# 07-KSZ9031_1G_BASET_XCVR.net
KiCad netlist of a schematic drawn in Altium Designer
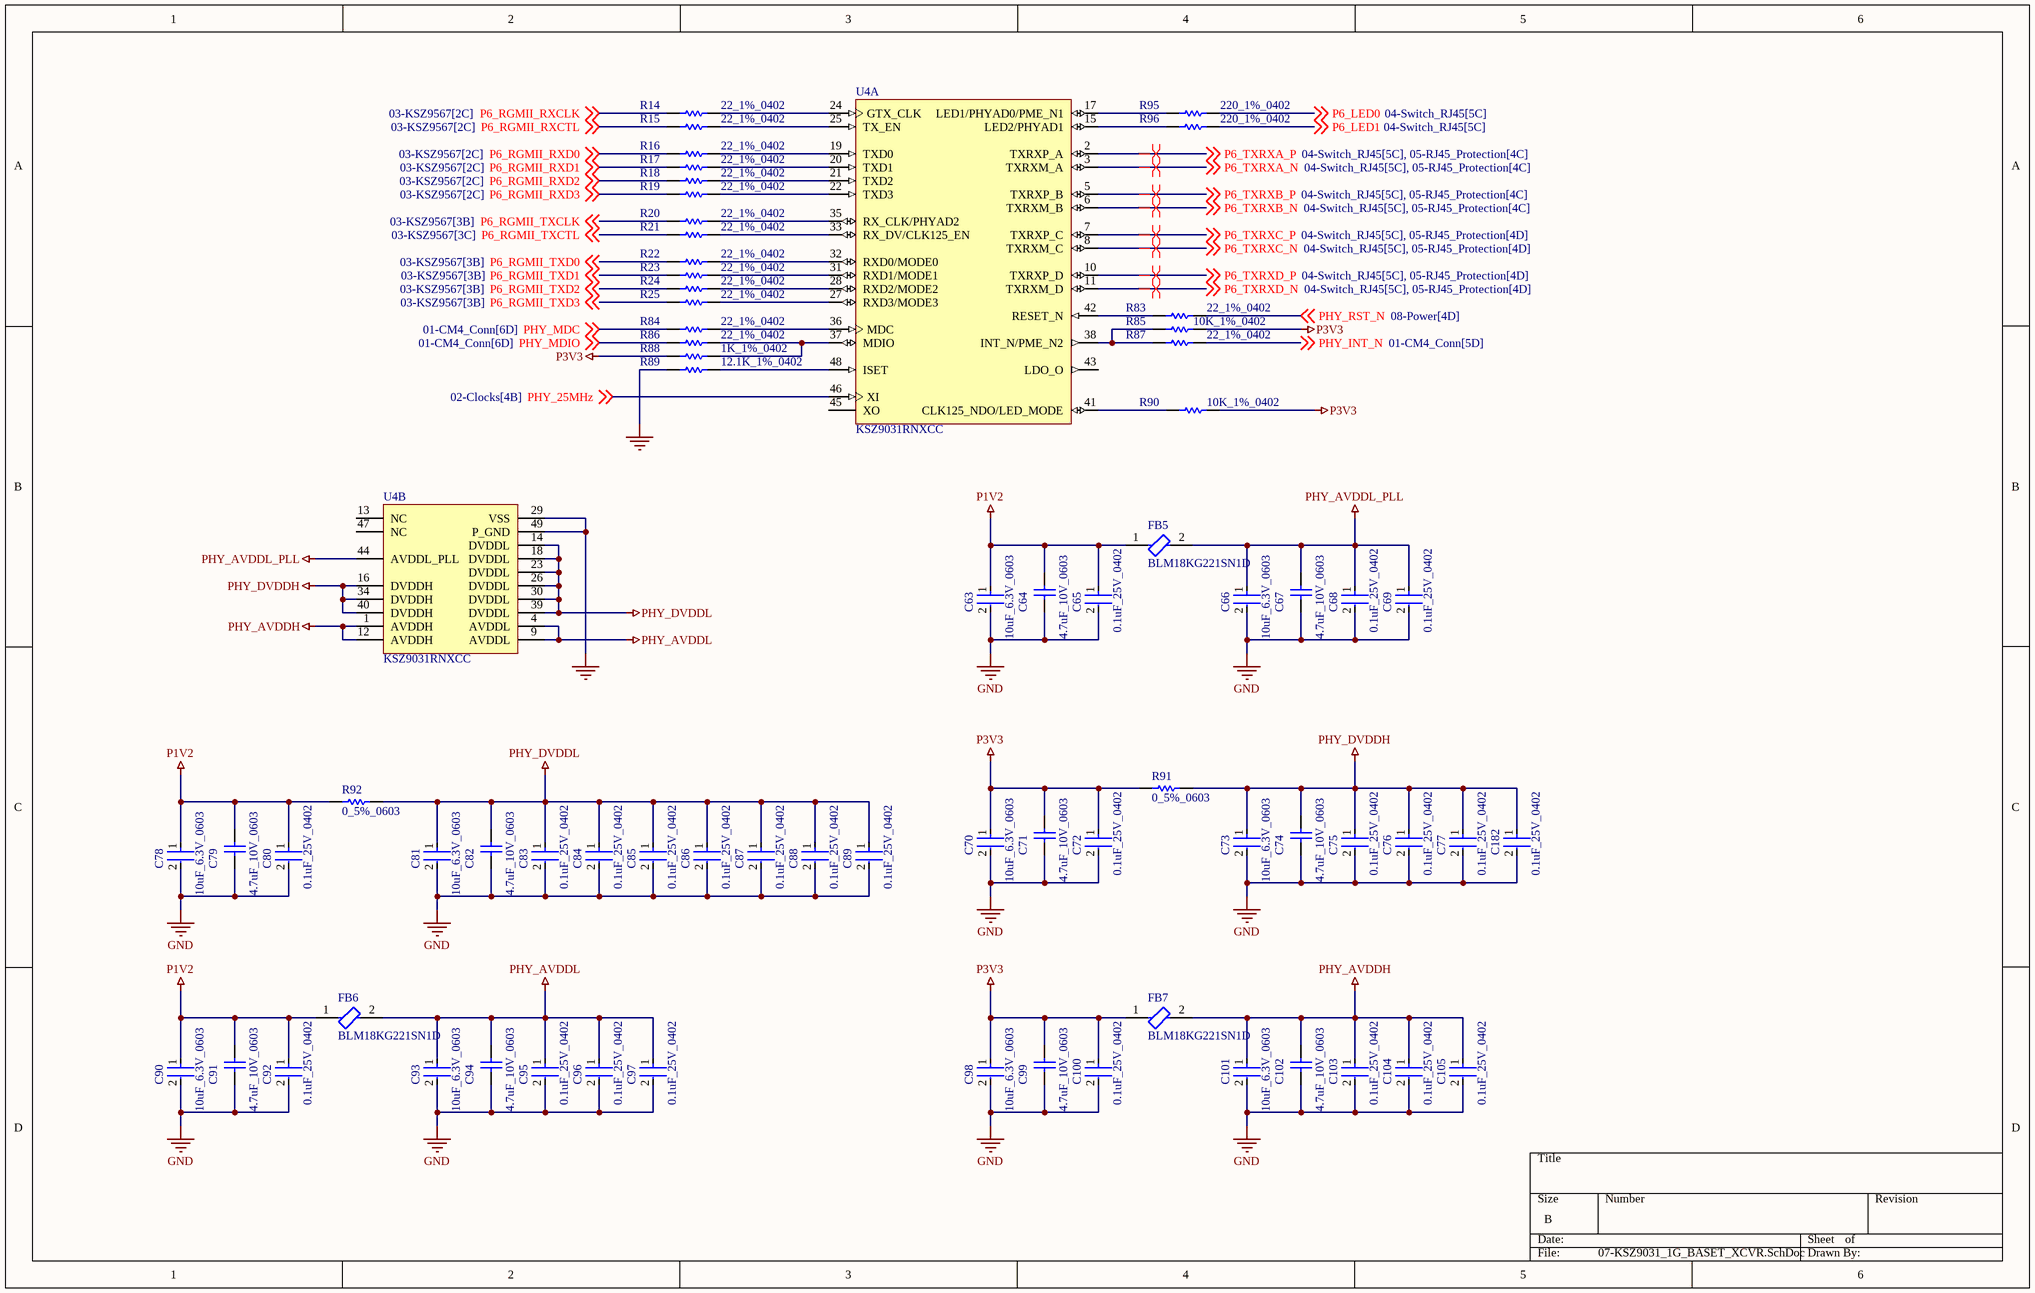
[diagram p0: 07-KSZ9031_1G_BASET_XCVR.SchDoc]

(export (version "E")
  (design (tool "Eeschema 10.0.6"))
  (components
    (comp (ref "C63")
      (value "10uF_6.3V_0603")
      (footprint "FP-C0603C106M9PACTU-MFG")
      (description "CAP CER 10UF 6.3V X5R 0603")
      (fields
        (field (name "MANUFACTURER PART NUMBER") "C0603C106M9PACTU")
        (field (name "MANUFACTURER") "Kemet")
      )
      (libsource (lib "Altium Content Vault") (part "b4654b650e69147ec39a6b967a45e02"))
    )
    (comp (ref "C64")
      (value "4.7uF_10V_0603")
      (footprint "CAPC1608X87X35NL15T15")
      (fields (field (name "PART NUMBER") "C0603C475K8PACTU") (field (name "MANUFACTURER") "Kemet"))
      (libsource (lib "Altium Content Vault") (part "CAP"))
    )
    (comp (ref "C65")
      (value "0.1uF_25V_0402")
      (footprint "FP-0402-L_1_0_1-W_0_5_0_1-IPC_C")
      (description "General Purpose Ceramic Capacitor, 0402, 100nF, 10%, X7R, 15%, 25V")
      (fields (field (name "VOLTAGE") "25V") (field (name "TOLERANCE") "10%"))
      (libsource (lib "Altium Content Vault") (part "b4654b650e69147ec39a6b967a45e02"))
    )
    (comp (ref "C66")
      (value "10uF_6.3V_0603")
      (footprint "FP-C0603C106M9PACTU-MFG")
      (description "CAP CER 10UF 6.3V X5R 0603")
      (fields
        (field (name "MANUFACTURER PART NUMBER") "C0603C106M9PACTU")
        (field (name "MANUFACTURER") "Kemet")
      )
      (libsource (lib "Altium Content Vault") (part "b4654b650e69147ec39a6b967a45e02"))
    )
    (comp (ref "C67")
      (value "4.7uF_10V_0603")
      (footprint "CAPC1608X87X35NL15T15")
      (fields (field (name "PART NUMBER") "C0603C475K8PACTU") (field (name "MANUFACTURER") "Kemet"))
      (libsource (lib "Altium Content Vault") (part "CAP"))
    )
    (comp (ref "C68")
      (value "0.1uF_25V_0402")
      (footprint "FP-0402-L_1_0_1-W_0_5_0_1-IPC_C")
      (description "General Purpose Ceramic Capacitor, 0402, 100nF, 10%, X7R, 15%, 25V")
      (fields (field (name "VOLTAGE") "25V") (field (name "TOLERANCE") "10%"))
      (libsource (lib "Altium Content Vault") (part "b4654b650e69147ec39a6b967a45e02"))
    )
    (comp (ref "C69")
      (value "0.1uF_25V_0402")
      (footprint "FP-0402-L_1_0_1-W_0_5_0_1-IPC_C")
      (description "General Purpose Ceramic Capacitor, 0402, 100nF, 10%, X7R, 15%, 25V")
      (fields (field (name "VOLTAGE") "25V") (field (name "TOLERANCE") "10%"))
      (libsource (lib "Altium Content Vault") (part "b4654b650e69147ec39a6b967a45e02"))
    )
    (comp (ref "C70")
      (value "10uF_6.3V_0603")
      (footprint "FP-C0603C106M9PACTU-MFG")
      (description "CAP CER 10UF 6.3V X5R 0603")
      (fields
        (field (name "MANUFACTURER PART NUMBER") "C0603C106M9PACTU")
        (field (name "MANUFACTURER") "Kemet")
      )
      (libsource (lib "Altium Content Vault") (part "b4654b650e69147ec39a6b967a45e02"))
    )
    (comp (ref "C71")
      (value "4.7uF_10V_0603")
      (footprint "CAPC1608X87X35NL15T15")
      (fields (field (name "PART NUMBER") "C0603C475K8PACTU") (field (name "MANUFACTURER") "Kemet"))
      (libsource (lib "Altium Content Vault") (part "CAP"))
    )
    (comp (ref "C72")
      (value "0.1uF_25V_0402")
      (footprint "FP-0402-L_1_0_1-W_0_5_0_1-IPC_C")
      (description "General Purpose Ceramic Capacitor, 0402, 100nF, 10%, X7R, 15%, 25V")
      (fields (field (name "VOLTAGE") "25V") (field (name "TOLERANCE") "10%"))
      (libsource (lib "Altium Content Vault") (part "b4654b650e69147ec39a6b967a45e02"))
    )
    (comp (ref "C73")
      (value "10uF_6.3V_0603")
      (footprint "FP-C0603C106M9PACTU-MFG")
      (description "CAP CER 10UF 6.3V X5R 0603")
      (fields
        (field (name "MANUFACTURER PART NUMBER") "C0603C106M9PACTU")
        (field (name "MANUFACTURER") "Kemet")
      )
      (libsource (lib "Altium Content Vault") (part "b4654b650e69147ec39a6b967a45e02"))
    )
    (comp (ref "C74")
      (value "4.7uF_10V_0603")
      (footprint "CAPC1608X87X35NL15T15")
      (fields (field (name "PART NUMBER") "C0603C475K8PACTU") (field (name "MANUFACTURER") "Kemet"))
      (libsource (lib "Altium Content Vault") (part "CAP"))
    )
    (comp (ref "C75")
      (value "0.1uF_25V_0402")
      (footprint "FP-0402-L_1_0_1-W_0_5_0_1-IPC_C")
      (description "General Purpose Ceramic Capacitor, 0402, 100nF, 10%, X7R, 15%, 25V")
      (fields (field (name "VOLTAGE") "25V") (field (name "TOLERANCE") "10%"))
      (libsource (lib "Altium Content Vault") (part "b4654b650e69147ec39a6b967a45e02"))
    )
    (comp (ref "C76")
      (value "0.1uF_25V_0402")
      (footprint "FP-0402-L_1_0_1-W_0_5_0_1-IPC_C")
      (description "General Purpose Ceramic Capacitor, 0402, 100nF, 10%, X7R, 15%, 25V")
      (fields (field (name "VOLTAGE") "25V") (field (name "TOLERANCE") "10%"))
      (libsource (lib "Altium Content Vault") (part "b4654b650e69147ec39a6b967a45e02"))
    )
    (comp (ref "C77")
      (value "0.1uF_25V_0402")
      (footprint "FP-0402-L_1_0_1-W_0_5_0_1-IPC_C")
      (description "General Purpose Ceramic Capacitor, 0402, 100nF, 10%, X7R, 15%, 25V")
      (fields (field (name "VOLTAGE") "25V") (field (name "TOLERANCE") "10%"))
      (libsource (lib "Altium Content Vault") (part "b4654b650e69147ec39a6b967a45e02"))
    )
    (comp (ref "C78")
      (value "10uF_6.3V_0603")
      (footprint "FP-C0603C106M9PACTU-MFG")
      (description "CAP CER 10UF 6.3V X5R 0603")
      (fields
        (field (name "MANUFACTURER PART NUMBER") "C0603C106M9PACTU")
        (field (name "MANUFACTURER") "Kemet")
      )
      (libsource (lib "Altium Content Vault") (part "b4654b650e69147ec39a6b967a45e02"))
    )
    (comp (ref "C79")
      (value "4.7uF_10V_0603")
      (footprint "CAPC1608X87X35NL15T15")
      (fields (field (name "PART NUMBER") "C0603C475K8PACTU") (field (name "MANUFACTURER") "Kemet"))
      (libsource (lib "Altium Content Vault") (part "CAP"))
    )
    (comp (ref "C80")
      (value "0.1uF_25V_0402")
      (footprint "FP-0402-L_1_0_1-W_0_5_0_1-IPC_C")
      (description "General Purpose Ceramic Capacitor, 0402, 100nF, 10%, X7R, 15%, 25V")
      (fields (field (name "VOLTAGE") "25V") (field (name "TOLERANCE") "10%"))
      (libsource (lib "Altium Content Vault") (part "b4654b650e69147ec39a6b967a45e02"))
    )
    (comp (ref "C81")
      (value "10uF_6.3V_0603")
      (footprint "FP-C0603C106M9PACTU-MFG")
      (description "CAP CER 10UF 6.3V X5R 0603")
      (fields
        (field (name "MANUFACTURER PART NUMBER") "C0603C106M9PACTU")
        (field (name "MANUFACTURER") "Kemet")
      )
      (libsource (lib "Altium Content Vault") (part "b4654b650e69147ec39a6b967a45e02"))
    )
    (comp (ref "C82")
      (value "4.7uF_10V_0603")
      (footprint "CAPC1608X87X35NL15T15")
      (fields (field (name "PART NUMBER") "C0603C475K8PACTU") (field (name "MANUFACTURER") "Kemet"))
      (libsource (lib "Altium Content Vault") (part "CAP"))
    )
    (comp (ref "C83")
      (value "0.1uF_25V_0402")
      (footprint "FP-0402-L_1_0_1-W_0_5_0_1-IPC_C")
      (description "General Purpose Ceramic Capacitor, 0402, 100nF, 10%, X7R, 15%, 25V")
      (fields (field (name "VOLTAGE") "25V") (field (name "TOLERANCE") "10%"))
      (libsource (lib "Altium Content Vault") (part "b4654b650e69147ec39a6b967a45e02"))
    )
    (comp (ref "C84")
      (value "0.1uF_25V_0402")
      (footprint "FP-0402-L_1_0_1-W_0_5_0_1-IPC_C")
      (description "General Purpose Ceramic Capacitor, 0402, 100nF, 10%, X7R, 15%, 25V")
      (fields (field (name "VOLTAGE") "25V") (field (name "TOLERANCE") "10%"))
      (libsource (lib "Altium Content Vault") (part "b4654b650e69147ec39a6b967a45e02"))
    )
    (comp (ref "C85")
      (value "0.1uF_25V_0402")
      (footprint "FP-0402-L_1_0_1-W_0_5_0_1-IPC_C")
      (description "General Purpose Ceramic Capacitor, 0402, 100nF, 10%, X7R, 15%, 25V")
      (fields (field (name "VOLTAGE") "25V") (field (name "TOLERANCE") "10%"))
      (libsource (lib "Altium Content Vault") (part "b4654b650e69147ec39a6b967a45e02"))
    )
    (comp (ref "C86")
      (value "0.1uF_25V_0402")
      (footprint "FP-0402-L_1_0_1-W_0_5_0_1-IPC_C")
      (description "General Purpose Ceramic Capacitor, 0402, 100nF, 10%, X7R, 15%, 25V")
      (fields (field (name "VOLTAGE") "25V") (field (name "TOLERANCE") "10%"))
      (libsource (lib "Altium Content Vault") (part "b4654b650e69147ec39a6b967a45e02"))
    )
    (comp (ref "C87")
      (value "0.1uF_25V_0402")
      (footprint "FP-0402-L_1_0_1-W_0_5_0_1-IPC_C")
      (description "General Purpose Ceramic Capacitor, 0402, 100nF, 10%, X7R, 15%, 25V")
      (fields (field (name "VOLTAGE") "25V") (field (name "TOLERANCE") "10%"))
      (libsource (lib "Altium Content Vault") (part "b4654b650e69147ec39a6b967a45e02"))
    )
    (comp (ref "C88")
      (value "0.1uF_25V_0402")
      (footprint "FP-0402-L_1_0_1-W_0_5_0_1-IPC_C")
      (description "General Purpose Ceramic Capacitor, 0402, 100nF, 10%, X7R, 15%, 25V")
      (fields (field (name "VOLTAGE") "25V") (field (name "TOLERANCE") "10%"))
      (libsource (lib "Altium Content Vault") (part "b4654b650e69147ec39a6b967a45e02"))
    )
    (comp (ref "C89")
      (value "0.1uF_25V_0402")
      (footprint "FP-0402-L_1_0_1-W_0_5_0_1-IPC_C")
      (description "General Purpose Ceramic Capacitor, 0402, 100nF, 10%, X7R, 15%, 25V")
      (fields (field (name "VOLTAGE") "25V") (field (name "TOLERANCE") "10%"))
      (libsource (lib "Altium Content Vault") (part "b4654b650e69147ec39a6b967a45e02"))
    )
    (comp (ref "C90")
      (value "10uF_6.3V_0603")
      (footprint "FP-C0603C106M9PACTU-MFG")
      (description "CAP CER 10UF 6.3V X5R 0603")
      (fields
        (field (name "MANUFACTURER PART NUMBER") "C0603C106M9PACTU")
        (field (name "MANUFACTURER") "Kemet")
      )
      (libsource (lib "Altium Content Vault") (part "b4654b650e69147ec39a6b967a45e02"))
    )
    (comp (ref "C91")
      (value "4.7uF_10V_0603")
      (footprint "CAPC1608X87X35NL15T15")
      (fields (field (name "PART NUMBER") "C0603C475K8PACTU") (field (name "MANUFACTURER") "Kemet"))
      (libsource (lib "Altium Content Vault") (part "CAP"))
    )
    (comp (ref "C92")
      (value "0.1uF_25V_0402")
      (footprint "FP-0402-L_1_0_1-W_0_5_0_1-IPC_C")
      (description "General Purpose Ceramic Capacitor, 0402, 100nF, 10%, X7R, 15%, 25V")
      (fields (field (name "VOLTAGE") "25V") (field (name "TOLERANCE") "10%"))
      (libsource (lib "Altium Content Vault") (part "b4654b650e69147ec39a6b967a45e02"))
    )
    (comp (ref "C93")
      (value "10uF_6.3V_0603")
      (footprint "FP-C0603C106M9PACTU-MFG")
      (description "CAP CER 10UF 6.3V X5R 0603")
      (fields
        (field (name "MANUFACTURER PART NUMBER") "C0603C106M9PACTU")
        (field (name "MANUFACTURER") "Kemet")
      )
      (libsource (lib "Altium Content Vault") (part "b4654b650e69147ec39a6b967a45e02"))
    )
    (comp (ref "C94")
      (value "4.7uF_10V_0603")
      (footprint "CAPC1608X87X35NL15T15")
      (fields (field (name "PART NUMBER") "C0603C475K8PACTU") (field (name "MANUFACTURER") "Kemet"))
      (libsource (lib "Altium Content Vault") (part "CAP"))
    )
    (comp (ref "C95")
      (value "0.1uF_25V_0402")
      (footprint "FP-0402-L_1_0_1-W_0_5_0_1-IPC_C")
      (description "General Purpose Ceramic Capacitor, 0402, 100nF, 10%, X7R, 15%, 25V")
      (fields (field (name "VOLTAGE") "25V") (field (name "TOLERANCE") "10%"))
      (libsource (lib "Altium Content Vault") (part "b4654b650e69147ec39a6b967a45e02"))
    )
    (comp (ref "C96")
      (value "0.1uF_25V_0402")
      (footprint "FP-0402-L_1_0_1-W_0_5_0_1-IPC_C")
      (description "General Purpose Ceramic Capacitor, 0402, 100nF, 10%, X7R, 15%, 25V")
      (fields (field (name "VOLTAGE") "25V") (field (name "TOLERANCE") "10%"))
      (libsource (lib "Altium Content Vault") (part "b4654b650e69147ec39a6b967a45e02"))
    )
    (comp (ref "C97")
      (value "0.1uF_25V_0402")
      (footprint "FP-0402-L_1_0_1-W_0_5_0_1-IPC_C")
      (description "General Purpose Ceramic Capacitor, 0402, 100nF, 10%, X7R, 15%, 25V")
      (fields (field (name "VOLTAGE") "25V") (field (name "TOLERANCE") "10%"))
      (libsource (lib "Altium Content Vault") (part "b4654b650e69147ec39a6b967a45e02"))
    )
    (comp (ref "C98")
      (value "10uF_6.3V_0603")
      (footprint "FP-C0603C106M9PACTU-MFG")
      (description "CAP CER 10UF 6.3V X5R 0603")
      (fields
        (field (name "MANUFACTURER PART NUMBER") "C0603C106M9PACTU")
        (field (name "MANUFACTURER") "Kemet")
      )
      (libsource (lib "Altium Content Vault") (part "b4654b650e69147ec39a6b967a45e02"))
    )
    (comp (ref "C99")
      (value "4.7uF_10V_0603")
      (footprint "CAPC1608X87X35NL15T15")
      (fields (field (name "PART NUMBER") "C0603C475K8PACTU") (field (name "MANUFACTURER") "Kemet"))
      (libsource (lib "Altium Content Vault") (part "CAP"))
    )
    (comp (ref "C100")
      (value "0.1uF_25V_0402")
      (footprint "FP-0402-L_1_0_1-W_0_5_0_1-IPC_C")
      (description "General Purpose Ceramic Capacitor, 0402, 100nF, 10%, X7R, 15%, 25V")
      (fields (field (name "VOLTAGE") "25V") (field (name "TOLERANCE") "10%"))
      (libsource (lib "Altium Content Vault") (part "b4654b650e69147ec39a6b967a45e02"))
    )
    (comp (ref "C101")
      (value "10uF_6.3V_0603")
      (footprint "FP-C0603C106M9PACTU-MFG")
      (description "CAP CER 10UF 6.3V X5R 0603")
      (fields
        (field (name "MANUFACTURER PART NUMBER") "C0603C106M9PACTU")
        (field (name "MANUFACTURER") "Kemet")
      )
      (libsource (lib "Altium Content Vault") (part "b4654b650e69147ec39a6b967a45e02"))
    )
    (comp (ref "C102")
      (value "4.7uF_10V_0603")
      (footprint "CAPC1608X87X35NL15T15")
      (fields (field (name "PART NUMBER") "C0603C475K8PACTU") (field (name "MANUFACTURER") "Kemet"))
      (libsource (lib "Altium Content Vault") (part "CAP"))
    )
    (comp (ref "C103")
      (value "0.1uF_25V_0402")
      (footprint "FP-0402-L_1_0_1-W_0_5_0_1-IPC_C")
      (description "General Purpose Ceramic Capacitor, 0402, 100nF, 10%, X7R, 15%, 25V")
      (fields (field (name "VOLTAGE") "25V") (field (name "TOLERANCE") "10%"))
      (libsource (lib "Altium Content Vault") (part "b4654b650e69147ec39a6b967a45e02"))
    )
    (comp (ref "C104")
      (value "0.1uF_25V_0402")
      (footprint "FP-0402-L_1_0_1-W_0_5_0_1-IPC_C")
      (description "General Purpose Ceramic Capacitor, 0402, 100nF, 10%, X7R, 15%, 25V")
      (fields (field (name "VOLTAGE") "25V") (field (name "TOLERANCE") "10%"))
      (libsource (lib "Altium Content Vault") (part "b4654b650e69147ec39a6b967a45e02"))
    )
    (comp (ref "C105")
      (value "0.1uF_25V_0402")
      (footprint "FP-0402-L_1_0_1-W_0_5_0_1-IPC_C")
      (description "General Purpose Ceramic Capacitor, 0402, 100nF, 10%, X7R, 15%, 25V")
      (fields (field (name "VOLTAGE") "25V") (field (name "TOLERANCE") "10%"))
      (libsource (lib "Altium Content Vault") (part "b4654b650e69147ec39a6b967a45e02"))
    )
    (comp (ref "C182")
      (value "0.1uF_25V_0402")
      (footprint "FP-0402-L_1_0_1-W_0_5_0_1-IPC_C")
      (description "General Purpose Ceramic Capacitor, 0402, 100nF, 10%, X7R, 15%, 25V")
      (fields (field (name "VOLTAGE") "25V") (field (name "TOLERANCE") "10%"))
      (libsource (lib "Altium Content Vault") (part "b4654b650e69147ec39a6b967a45e02"))
    )
    (comp (ref "FB5")
      (value "BLM18KG221SN1D")
      (footprint "FP-BLM18-0_15-t0_8-IPC_B")
      (description "Chip Ferrite Bead, 0603, 220Ω @ 100MHz, 0.05Ω, 25%, 2.2A")
      (fields (field (name "TOLERANCE") "25%"))
      (libsource (lib "Altium Content Vault") (part "5f30dd21d616792df468990f7003faa"))
    )
    (comp (ref "FB6")
      (value "BLM18KG221SN1D")
      (footprint "FP-BLM18-0_15-t0_8-IPC_B")
      (description "Chip Ferrite Bead, 0603, 220Ω @ 100MHz, 0.05Ω, 25%, 2.2A")
      (fields (field (name "TOLERANCE") "25%"))
      (libsource (lib "Altium Content Vault") (part "5f30dd21d616792df468990f7003faa"))
    )
    (comp (ref "FB7")
      (value "BLM18KG221SN1D")
      (footprint "FP-BLM18-0_15-t0_8-IPC_B")
      (description "Chip Ferrite Bead, 0603, 220Ω @ 100MHz, 0.05Ω, 25%, 2.2A")
      (fields (field (name "TOLERANCE") "25%"))
      (libsource (lib "Altium Content Vault") (part "5f30dd21d616792df468990f7003faa"))
    )
    (comp (ref "R14")
      (value "22_1%_0402")
      (footprint "RESC1005X40X25ML05T10")
      (fields (field (name "PART NUMBER") "RC0402FR-1322RL") (field (name "MANUFACTURER") "Yageo / Phycomp"))
      (libsource (lib "Altium Content Vault") (part "RES"))
    )
    (comp (ref "R15")
      (value "22_1%_0402")
      (footprint "RESC1005X40X25ML05T10")
      (fields (field (name "PART NUMBER") "RC0402FR-1322RL") (field (name "MANUFACTURER") "Yageo / Phycomp"))
      (libsource (lib "Altium Content Vault") (part "RES"))
    )
    (comp (ref "R16")
      (value "22_1%_0402")
      (footprint "RESC1005X40X25ML05T10")
      (fields (field (name "PART NUMBER") "RC0402FR-1322RL") (field (name "MANUFACTURER") "Yageo / Phycomp"))
      (libsource (lib "Altium Content Vault") (part "RES"))
    )
    (comp (ref "R17")
      (value "22_1%_0402")
      (footprint "RESC1005X40X25ML05T10")
      (fields (field (name "PART NUMBER") "RC0402FR-1322RL") (field (name "MANUFACTURER") "Yageo / Phycomp"))
      (libsource (lib "Altium Content Vault") (part "RES"))
    )
    (comp (ref "R18")
      (value "22_1%_0402")
      (footprint "RESC1005X40X25ML05T10")
      (fields (field (name "PART NUMBER") "RC0402FR-1322RL") (field (name "MANUFACTURER") "Yageo / Phycomp"))
      (libsource (lib "Altium Content Vault") (part "RES"))
    )
    (comp (ref "R19")
      (value "22_1%_0402")
      (footprint "RESC1005X40X25ML05T10")
      (fields (field (name "PART NUMBER") "RC0402FR-1322RL") (field (name "MANUFACTURER") "Yageo / Phycomp"))
      (libsource (lib "Altium Content Vault") (part "RES"))
    )
    (comp (ref "R20")
      (value "22_1%_0402")
      (footprint "RESC1005X40X25ML05T10")
      (fields (field (name "PART NUMBER") "RC0402FR-1322RL") (field (name "MANUFACTURER") "Yageo / Phycomp"))
      (libsource (lib "Altium Content Vault") (part "RES"))
    )
    (comp (ref "R21")
      (value "22_1%_0402")
      (footprint "RESC1005X40X25ML05T10")
      (fields (field (name "PART NUMBER") "RC0402FR-1322RL") (field (name "MANUFACTURER") "Yageo / Phycomp"))
      (libsource (lib "Altium Content Vault") (part "RES"))
    )
    (comp (ref "R22")
      (value "22_1%_0402")
      (footprint "RESC1005X40X25ML05T10")
      (fields (field (name "PART NUMBER") "RC0402FR-1322RL") (field (name "MANUFACTURER") "Yageo / Phycomp"))
      (libsource (lib "Altium Content Vault") (part "RES"))
    )
    (comp (ref "R23")
      (value "22_1%_0402")
      (footprint "RESC1005X40X25ML05T10")
      (fields (field (name "PART NUMBER") "RC0402FR-1322RL") (field (name "MANUFACTURER") "Yageo / Phycomp"))
      (libsource (lib "Altium Content Vault") (part "RES"))
    )
    (comp (ref "R24")
      (value "22_1%_0402")
      (footprint "RESC1005X40X25ML05T10")
      (fields (field (name "PART NUMBER") "RC0402FR-1322RL") (field (name "MANUFACTURER") "Yageo / Phycomp"))
      (libsource (lib "Altium Content Vault") (part "RES"))
    )
    (comp (ref "R25")
      (value "22_1%_0402")
      (footprint "RESC1005X40X25ML05T10")
      (fields (field (name "PART NUMBER") "RC0402FR-1322RL") (field (name "MANUFACTURER") "Yageo / Phycomp"))
      (libsource (lib "Altium Content Vault") (part "RES"))
    )
    (comp (ref "R83")
      (value "22_1%_0402")
      (footprint "RESC1005X40X25ML05T10")
      (fields (field (name "PART NUMBER") "RC0402FR-1322RL") (field (name "MANUFACTURER") "Yageo / Phycomp"))
      (libsource (lib "Altium Content Vault") (part "RES"))
    )
    (comp (ref "R84")
      (value "22_1%_0402")
      (footprint "RESC1005X40X25ML05T10")
      (fields (field (name "PART NUMBER") "RC0402FR-1322RL") (field (name "MANUFACTURER") "Yageo / Phycomp"))
      (libsource (lib "Altium Content Vault") (part "RES"))
    )
    (comp (ref "R85")
      (value "10K_1%_0402")
      (footprint "RESC1005X40X25NL10T10")
      (fields (field (name "MANUFACTURER") "Bourns") (field (name "PART NUMBER") "CR0402-FX-1002GLF"))
      (libsource (lib "Altium Content Vault") (part "RES"))
    )
    (comp (ref "R86")
      (value "22_1%_0402")
      (footprint "RESC1005X40X25ML05T10")
      (fields (field (name "PART NUMBER") "RC0402FR-1322RL") (field (name "MANUFACTURER") "Yageo / Phycomp"))
      (libsource (lib "Altium Content Vault") (part "RES"))
    )
    (comp (ref "R87")
      (value "22_1%_0402")
      (footprint "RESC1005X40X25ML05T10")
      (fields (field (name "PART NUMBER") "RC0402FR-1322RL") (field (name "MANUFACTURER") "Yageo / Phycomp"))
      (libsource (lib "Altium Content Vault") (part "RES"))
    )
    (comp (ref "R88")
      (value "1K_1%_0402")
      (footprint "RESC1005X40X25ML05T10")
      (fields (field (name "MANUFACTURER") "Multicomp") (field (name "PART NUMBER") "MCMR04X1001FTL"))
      (libsource (lib "Altium Content Vault") (part "RES"))
    )
    (comp (ref "R89")
      (value "12.1K_1%_0402")
      (footprint "RESC1005X40X25NL10T10")
      (fields (field (name "MANUFACTURER") "Multicomp") (field (name "PART NUMBER") "MC00625W0402112K1"))
      (libsource (lib "Altium Content Vault") (part "RES"))
    )
    (comp (ref "R90")
      (value "10K_1%_0402")
      (footprint "RESC1005X40X25NL10T10")
      (fields (field (name "MANUFACTURER") "Bourns") (field (name "PART NUMBER") "CR0402-FX-1002GLF"))
      (libsource (lib "Altium Content Vault") (part "RES"))
    )
    (comp (ref "R91")
      (value "0_5%_0603")
      (footprint "RESC1608X55X25ML10T15")
      (description "Chip Resistor, 0 Ohm, +/- 5%, 0.1 W, -55 to 155 degC, 0603 (1608 Metric), RoHS, Tape and Reel")
      (fields (field (name "TOLERANCE") "5%") (field (name "MANUFACTURER") "Yageo"))
      (libsource (lib "Altium Content Vault") (part "RES-2"))
    )
    (comp (ref "R92")
      (value "0_5%_0603")
      (footprint "RESC1608X55X25ML10T15")
      (description "Chip Resistor, 0 Ohm, +/- 5%, 0.1 W, -55 to 155 degC, 0603 (1608 Metric), RoHS, Tape and Reel")
      (fields (field (name "TOLERANCE") "5%") (field (name "MANUFACTURER") "Yageo"))
      (libsource (lib "Altium Content Vault") (part "RES-2"))
    )
    (comp (ref "R95")
      (value "220_1%_0402")
      (footprint "RESC1005X40X25NL05T10")
      (fields (field (name "MANUFACTURER") "Yageo / Phycomp") (field (name "PART NUMBER") "RC0402JR-07220RL"))
      (libsource (lib "Altium Content Vault") (part "RES"))
    )
    (comp (ref "R96")
      (value "220_1%_0402")
      (footprint "RESC1005X40X25NL05T10")
      (fields (field (name "MANUFACTURER") "Yageo / Phycomp") (field (name "PART NUMBER") "RC0402JR-07220RL"))
      (libsource (lib "Altium Content Vault") (part "RES"))
    )
    (comp (ref "U4")
      (value "KSZ9031RNXCC")
      (footprint "MICL-QFN-48_V")
      (description "Gigabit Ethernet Transceiver with RGMII Support, 1.14 to 1.26 V, 0 to 70 degC, 48-Pin QFN, RoHS")
      (fields (field (name "MANUFACTURER") "Micrel"))
      (libsource (lib "Altium Content Vault") (part "MICL-KSZ9031RNX-48"))
    )
  )
  (nets
    (net (code "1") (name "GND") (class "Default")
      (node (ref "C100") (pin "2") (pinfunction "2_2") (pintype "passive"))
      (node (ref "C101") (pin "2") (pinfunction "2_2") (pintype "passive"))
      (node (ref "C102") (pin "1") (pinfunction "1_1") (pintype "passive"))
      (node (ref "C103") (pin "2") (pinfunction "2_2") (pintype "passive"))
      (node (ref "C104") (pin "2") (pinfunction "2_2") (pintype "passive"))
      (node (ref "C105") (pin "2") (pinfunction "2_2") (pintype "passive"))
      (node (ref "C182") (pin "2") (pinfunction "2_2") (pintype "passive"))
      (node (ref "C63") (pin "2") (pinfunction "2_2") (pintype "passive"))
      (node (ref "C64") (pin "1") (pinfunction "1_1") (pintype "passive"))
      (node (ref "C65") (pin "2") (pinfunction "2_2") (pintype "passive"))
      (node (ref "C66") (pin "2") (pinfunction "2_2") (pintype "passive"))
      (node (ref "C67") (pin "1") (pinfunction "1_1") (pintype "passive"))
      (node (ref "C68") (pin "2") (pinfunction "2_2") (pintype "passive"))
      (node (ref "C69") (pin "2") (pinfunction "2_2") (pintype "passive"))
      (node (ref "C70") (pin "2") (pinfunction "2_2") (pintype "passive"))
      (node (ref "C71") (pin "1") (pinfunction "1_1") (pintype "passive"))
      (node (ref "C72") (pin "2") (pinfunction "2_2") (pintype "passive"))
      (node (ref "C73") (pin "2") (pinfunction "2_2") (pintype "passive"))
      (node (ref "C74") (pin "1") (pinfunction "1_1") (pintype "passive"))
      (node (ref "C75") (pin "2") (pinfunction "2_2") (pintype "passive"))
      (node (ref "C76") (pin "2") (pinfunction "2_2") (pintype "passive"))
      (node (ref "C77") (pin "2") (pinfunction "2_2") (pintype "passive"))
      (node (ref "C78") (pin "2") (pinfunction "2_2") (pintype "passive"))
      (node (ref "C79") (pin "1") (pinfunction "1_1") (pintype "passive"))
      (node (ref "C80") (pin "2") (pinfunction "2_2") (pintype "passive"))
      (node (ref "C81") (pin "2") (pinfunction "2_2") (pintype "passive"))
      (node (ref "C82") (pin "1") (pinfunction "1_1") (pintype "passive"))
      (node (ref "C83") (pin "2") (pinfunction "2_2") (pintype "passive"))
      (node (ref "C84") (pin "2") (pinfunction "2_2") (pintype "passive"))
      (node (ref "C85") (pin "2") (pinfunction "2_2") (pintype "passive"))
      (node (ref "C86") (pin "2") (pinfunction "2_2") (pintype "passive"))
      (node (ref "C87") (pin "2") (pinfunction "2_2") (pintype "passive"))
      (node (ref "C88") (pin "2") (pinfunction "2_2") (pintype "passive"))
      (node (ref "C89") (pin "2") (pinfunction "2_2") (pintype "passive"))
      (node (ref "C90") (pin "2") (pinfunction "2_2") (pintype "passive"))
      (node (ref "C91") (pin "1") (pinfunction "1_1") (pintype "passive"))
      (node (ref "C92") (pin "2") (pinfunction "2_2") (pintype "passive"))
      (node (ref "C93") (pin "2") (pinfunction "2_2") (pintype "passive"))
      (node (ref "C94") (pin "1") (pinfunction "1_1") (pintype "passive"))
      (node (ref "C95") (pin "2") (pinfunction "2_2") (pintype "passive"))
      (node (ref "C96") (pin "2") (pinfunction "2_2") (pintype "passive"))
      (node (ref "C97") (pin "2") (pinfunction "2_2") (pintype "passive"))
      (node (ref "C98") (pin "2") (pinfunction "2_2") (pintype "passive"))
      (node (ref "C99") (pin "1") (pinfunction "1_1") (pintype "passive"))
      (node (ref "R89") (pin "1") (pinfunction "1_1") (pintype "passive"))
      (node (ref "U4") (pin "29") (pinfunction "VSS_29") (pintype "power_in"))
      (node (ref "U4") (pin "49") (pinfunction "P_GND_49") (pintype "power_in"))
    )
    (net (code "2") (name "Net-(U4A-CLK125_NDO{slash}LED_MODE)") (class "Default")
      (node (ref "R90") (pin "1") (pinfunction "1_1") (pintype "passive"))
      (node (ref "U4") (pin "41") (pinfunction "CLK125_NDO/LED_MODE_41") (pintype "bidirectional"))
    )
    (net (code "3") (name "Net-(U4A-GTX_CLK)") (class "Default")
      (node (ref "R14") (pin "2") (pinfunction "2_2") (pintype "passive"))
      (node (ref "U4") (pin "24") (pinfunction "GTX_CLK_24") (pintype "input"))
    )
    (net (code "4") (name "Net-(U4A-INT_N{slash}PME_N2)") (class "Default")
      (node (ref "R85") (pin "1") (pinfunction "1_1") (pintype "passive"))
      (node (ref "R87") (pin "1") (pinfunction "1_1") (pintype "passive"))
      (node (ref "U4") (pin "38") (pinfunction "INT_N/PME_N2_38") (pintype "output"))
    )
    (net (code "5") (name "Net-(U4A-ISET)") (class "Default")
      (node (ref "R89") (pin "2") (pinfunction "2_2") (pintype "passive"))
      (node (ref "U4") (pin "48") (pinfunction "ISET_48") (pintype "input"))
    )
    (net (code "6") (name "Net-(U4A-LED1{slash}PHYAD0{slash}PME_N1)") (class "Default")
      (node (ref "R95") (pin "1") (pinfunction "1_1") (pintype "passive"))
      (node (ref "U4") (pin "17") (pinfunction "LED1/PHYAD0/PME_N1_17") (pintype "bidirectional"))
    )
    (net (code "7") (name "Net-(U4A-LED2{slash}PHYAD1)") (class "Default")
      (node (ref "R96") (pin "1") (pinfunction "1_1") (pintype "passive"))
      (node (ref "U4") (pin "15") (pinfunction "LED2/PHYAD1_15") (pintype "bidirectional"))
    )
    (net (code "8") (name "Net-(U4A-MDC)") (class "Default")
      (node (ref "R84") (pin "2") (pinfunction "2_2") (pintype "passive"))
      (node (ref "U4") (pin "36") (pinfunction "MDC_36") (pintype "input"))
    )
    (net (code "9") (name "Net-(U4A-MDIO)") (class "Default")
      (node (ref "R86") (pin "2") (pinfunction "2_2") (pintype "passive"))
      (node (ref "R88") (pin "2") (pinfunction "2_2") (pintype "passive"))
      (node (ref "U4") (pin "37") (pinfunction "MDIO_37") (pintype "bidirectional"))
    )
    (net (code "10") (name "Net-(U4A-RESET_N)") (class "Default")
      (node (ref "R83") (pin "1") (pinfunction "1_1") (pintype "passive"))
      (node (ref "U4") (pin "42") (pinfunction "RESET_N_42") (pintype "input"))
    )
    (net (code "11") (name "Net-(U4A-RXD0{slash}MODE0)") (class "Default")
      (node (ref "R22") (pin "2") (pinfunction "2_2") (pintype "passive"))
      (node (ref "U4") (pin "32") (pinfunction "RXD0/MODE0_32") (pintype "bidirectional"))
    )
    (net (code "12") (name "Net-(U4A-RXD1{slash}MODE1)") (class "Default")
      (node (ref "R23") (pin "2") (pinfunction "2_2") (pintype "passive"))
      (node (ref "U4") (pin "31") (pinfunction "RXD1/MODE1_31") (pintype "bidirectional"))
    )
    (net (code "13") (name "Net-(U4A-RXD2{slash}MODE2)") (class "Default")
      (node (ref "R24") (pin "2") (pinfunction "2_2") (pintype "passive"))
      (node (ref "U4") (pin "28") (pinfunction "RXD2/MODE2_28") (pintype "bidirectional"))
    )
    (net (code "14") (name "Net-(U4A-RXD3{slash}MODE3)") (class "Default")
      (node (ref "R25") (pin "2") (pinfunction "2_2") (pintype "passive"))
      (node (ref "U4") (pin "27") (pinfunction "RXD3/MODE3_27") (pintype "bidirectional"))
    )
    (net (code "15") (name "Net-(U4A-RX_CLK{slash}PHYAD2)") (class "Default")
      (node (ref "R20") (pin "2") (pinfunction "2_2") (pintype "passive"))
      (node (ref "U4") (pin "35") (pinfunction "RX_CLK/PHYAD2_35") (pintype "bidirectional"))
    )
    (net (code "16") (name "Net-(U4A-RX_DV{slash}CLK125_EN)") (class "Default")
      (node (ref "R21") (pin "2") (pinfunction "2_2") (pintype "passive"))
      (node (ref "U4") (pin "33") (pinfunction "RX_DV/CLK125_EN_33") (pintype "bidirectional"))
    )
    (net (code "17") (name "Net-(U4A-TXD0)") (class "Default")
      (node (ref "R16") (pin "2") (pinfunction "2_2") (pintype "passive"))
      (node (ref "U4") (pin "19") (pinfunction "TXD0_19") (pintype "input"))
    )
    (net (code "18") (name "Net-(U4A-TXD1)") (class "Default")
      (node (ref "R17") (pin "2") (pinfunction "2_2") (pintype "passive"))
      (node (ref "U4") (pin "20") (pinfunction "TXD1_20") (pintype "input"))
    )
    (net (code "19") (name "Net-(U4A-TXD2)") (class "Default")
      (node (ref "R18") (pin "2") (pinfunction "2_2") (pintype "passive"))
      (node (ref "U4") (pin "21") (pinfunction "TXD2_21") (pintype "input"))
    )
    (net (code "20") (name "Net-(U4A-TXD3)") (class "Default")
      (node (ref "R19") (pin "2") (pinfunction "2_2") (pintype "passive"))
      (node (ref "U4") (pin "22") (pinfunction "TXD3_22") (pintype "input"))
    )
    (net (code "21") (name "Net-(U4A-TX_EN)") (class "Default")
      (node (ref "R15") (pin "2") (pinfunction "2_2") (pintype "passive"))
      (node (ref "U4") (pin "25") (pinfunction "TX_EN_25") (pintype "input"))
    )
    (net (code "22") (name "P1V2") (class "Default")
      (node (ref "C63") (pin "1") (pinfunction "1_1") (pintype "passive"))
      (node (ref "C64") (pin "2") (pinfunction "2_2") (pintype "passive"))
      (node (ref "C65") (pin "1") (pinfunction "1_1") (pintype "passive"))
      (node (ref "C78") (pin "1") (pinfunction "1_1") (pintype "passive"))
      (node (ref "C79") (pin "2") (pinfunction "2_2") (pintype "passive"))
      (node (ref "C80") (pin "1") (pinfunction "1_1") (pintype "passive"))
      (node (ref "C90") (pin "1") (pinfunction "1_1") (pintype "passive"))
      (node (ref "C91") (pin "2") (pinfunction "2_2") (pintype "passive"))
      (node (ref "C92") (pin "1") (pinfunction "1_1") (pintype "passive"))
      (node (ref "FB5") (pin "1") (pinfunction "1_1") (pintype "passive"))
      (node (ref "FB6") (pin "1") (pinfunction "1_1") (pintype "passive"))
      (node (ref "R92") (pin "1") (pinfunction "1_1") (pintype "passive"))
    )
    (net (code "23") (name "P3V3") (class "Default")
      (node (ref "C100") (pin "1") (pinfunction "1_1") (pintype "passive"))
      (node (ref "C70") (pin "1") (pinfunction "1_1") (pintype "passive"))
      (node (ref "C71") (pin "2") (pinfunction "2_2") (pintype "passive"))
      (node (ref "C72") (pin "1") (pinfunction "1_1") (pintype "passive"))
      (node (ref "C98") (pin "1") (pinfunction "1_1") (pintype "passive"))
      (node (ref "C99") (pin "2") (pinfunction "2_2") (pintype "passive"))
      (node (ref "FB7") (pin "1") (pinfunction "1_1") (pintype "passive"))
      (node (ref "R85") (pin "2") (pinfunction "2_2") (pintype "passive"))
      (node (ref "R88") (pin "1") (pinfunction "1_1") (pintype "passive"))
      (node (ref "R90") (pin "2") (pinfunction "2_2") (pintype "passive"))
      (node (ref "R91") (pin "1") (pinfunction "1_1") (pintype "passive"))
    )
    (net (code "24") (name "P6_LED0") (class "Default")
      (node (ref "R95") (pin "2") (pinfunction "2_2") (pintype "passive"))
    )
    (net (code "25") (name "P6_LED1") (class "Default")
      (node (ref "R96") (pin "2") (pinfunction "2_2") (pintype "passive"))
    )
    (net (code "26") (name "P6_RGMII_RXCLK") (class "Default")
      (node (ref "R14") (pin "1") (pinfunction "1_1") (pintype "passive"))
    )
    (net (code "27") (name "P6_RGMII_RXCTL") (class "Default")
      (node (ref "R15") (pin "1") (pinfunction "1_1") (pintype "passive"))
    )
    (net (code "28") (name "P6_RGMII_RXD0") (class "Default")
      (node (ref "R16") (pin "1") (pinfunction "1_1") (pintype "passive"))
    )
    (net (code "29") (name "P6_RGMII_RXD1") (class "Default")
      (node (ref "R17") (pin "1") (pinfunction "1_1") (pintype "passive"))
    )
    (net (code "30") (name "P6_RGMII_RXD2") (class "Default")
      (node (ref "R18") (pin "1") (pinfunction "1_1") (pintype "passive"))
    )
    (net (code "31") (name "P6_RGMII_RXD3") (class "Default")
      (node (ref "R19") (pin "1") (pinfunction "1_1") (pintype "passive"))
    )
    (net (code "32") (name "P6_RGMII_TXCLK") (class "Default")
      (node (ref "R20") (pin "1") (pinfunction "1_1") (pintype "passive"))
    )
    (net (code "33") (name "P6_RGMII_TXCTL") (class "Default")
      (node (ref "R21") (pin "1") (pinfunction "1_1") (pintype "passive"))
    )
    (net (code "34") (name "P6_RGMII_TXD0") (class "Default")
      (node (ref "R22") (pin "1") (pinfunction "1_1") (pintype "passive"))
    )
    (net (code "35") (name "P6_RGMII_TXD1") (class "Default")
      (node (ref "R23") (pin "1") (pinfunction "1_1") (pintype "passive"))
    )
    (net (code "36") (name "P6_RGMII_TXD2") (class "Default")
      (node (ref "R24") (pin "1") (pinfunction "1_1") (pintype "passive"))
    )
    (net (code "37") (name "P6_RGMII_TXD3") (class "Default")
      (node (ref "R25") (pin "1") (pinfunction "1_1") (pintype "passive"))
    )
    (net (code "38") (name "P6_TXRXA_N") (class "Default")
      (node (ref "U4") (pin "3") (pinfunction "TXRXM_A_3") (pintype "bidirectional"))
    )
    (net (code "39") (name "P6_TXRXA_P") (class "Default")
      (node (ref "U4") (pin "2") (pinfunction "TXRXP_A_2") (pintype "bidirectional"))
    )
    (net (code "40") (name "P6_TXRXB_N") (class "Default")
      (node (ref "U4") (pin "6") (pinfunction "TXRXM_B_6") (pintype "bidirectional"))
    )
    (net (code "41") (name "P6_TXRXB_P") (class "Default")
      (node (ref "U4") (pin "5") (pinfunction "TXRXP_B_5") (pintype "bidirectional"))
    )
    (net (code "42") (name "P6_TXRXC_N") (class "Default")
      (node (ref "U4") (pin "8") (pinfunction "TXRXM_C_8") (pintype "bidirectional"))
    )
    (net (code "43") (name "P6_TXRXC_P") (class "Default")
      (node (ref "U4") (pin "7") (pinfunction "TXRXP_C_7") (pintype "bidirectional"))
    )
    (net (code "44") (name "P6_TXRXD_N") (class "Default")
      (node (ref "U4") (pin "11") (pinfunction "TXRXM_D_11") (pintype "bidirectional"))
    )
    (net (code "45") (name "P6_TXRXD_P") (class "Default")
      (node (ref "U4") (pin "10") (pinfunction "TXRXP_D_10") (pintype "bidirectional"))
    )
    (net (code "46") (name "PHY_25MHz") (class "Default")
      (node (ref "U4") (pin "46") (pinfunction "XI_46") (pintype "input"))
    )
    (net (code "47") (name "PHY_AVDDH") (class "Default")
      (node (ref "C101") (pin "1") (pinfunction "1_1") (pintype "passive"))
      (node (ref "C102") (pin "2") (pinfunction "2_2") (pintype "passive"))
      (node (ref "C103") (pin "1") (pinfunction "1_1") (pintype "passive"))
      (node (ref "C104") (pin "1") (pinfunction "1_1") (pintype "passive"))
      (node (ref "C105") (pin "1") (pinfunction "1_1") (pintype "passive"))
      (node (ref "FB7") (pin "2") (pinfunction "2_2") (pintype "passive"))
      (node (ref "U4") (pin "1") (pinfunction "AVDDH_1") (pintype "power_in"))
      (node (ref "U4") (pin "12") (pinfunction "AVDDH_12") (pintype "power_in"))
    )
    (net (code "48") (name "PHY_AVDDL") (class "Default")
      (node (ref "C93") (pin "1") (pinfunction "1_1") (pintype "passive"))
      (node (ref "C94") (pin "2") (pinfunction "2_2") (pintype "passive"))
      (node (ref "C95") (pin "1") (pinfunction "1_1") (pintype "passive"))
      (node (ref "C96") (pin "1") (pinfunction "1_1") (pintype "passive"))
      (node (ref "C97") (pin "1") (pinfunction "1_1") (pintype "passive"))
      (node (ref "FB6") (pin "2") (pinfunction "2_2") (pintype "passive"))
      (node (ref "U4") (pin "4") (pinfunction "AVDDL_4") (pintype "power_in"))
      (node (ref "U4") (pin "9") (pinfunction "AVDDL_9") (pintype "power_in"))
    )
    (net (code "49") (name "PHY_AVDDL_PLL") (class "Default")
      (node (ref "C66") (pin "1") (pinfunction "1_1") (pintype "passive"))
      (node (ref "C67") (pin "2") (pinfunction "2_2") (pintype "passive"))
      (node (ref "C68") (pin "1") (pinfunction "1_1") (pintype "passive"))
      (node (ref "C69") (pin "1") (pinfunction "1_1") (pintype "passive"))
      (node (ref "FB5") (pin "2") (pinfunction "2_2") (pintype "passive"))
      (node (ref "U4") (pin "44") (pinfunction "AVDDL_PLL_44") (pintype "power_in"))
    )
    (net (code "50") (name "PHY_DVDDH") (class "Default")
      (node (ref "C182") (pin "1") (pinfunction "1_1") (pintype "passive"))
      (node (ref "C73") (pin "1") (pinfunction "1_1") (pintype "passive"))
      (node (ref "C74") (pin "2") (pinfunction "2_2") (pintype "passive"))
      (node (ref "C75") (pin "1") (pinfunction "1_1") (pintype "passive"))
      (node (ref "C76") (pin "1") (pinfunction "1_1") (pintype "passive"))
      (node (ref "C77") (pin "1") (pinfunction "1_1") (pintype "passive"))
      (node (ref "R91") (pin "2") (pinfunction "2_2") (pintype "passive"))
      (node (ref "U4") (pin "16") (pinfunction "DVDDH_16") (pintype "power_in"))
      (node (ref "U4") (pin "34") (pinfunction "DVDDH_34") (pintype "power_in"))
      (node (ref "U4") (pin "40") (pinfunction "DVDDH_40") (pintype "power_in"))
    )
    (net (code "51") (name "PHY_DVDDL") (class "Default")
      (node (ref "C81") (pin "1") (pinfunction "1_1") (pintype "passive"))
      (node (ref "C82") (pin "2") (pinfunction "2_2") (pintype "passive"))
      (node (ref "C83") (pin "1") (pinfunction "1_1") (pintype "passive"))
      (node (ref "C84") (pin "1") (pinfunction "1_1") (pintype "passive"))
      (node (ref "C85") (pin "1") (pinfunction "1_1") (pintype "passive"))
      (node (ref "C86") (pin "1") (pinfunction "1_1") (pintype "passive"))
      (node (ref "C87") (pin "1") (pinfunction "1_1") (pintype "passive"))
      (node (ref "C88") (pin "1") (pinfunction "1_1") (pintype "passive"))
      (node (ref "C89") (pin "1") (pinfunction "1_1") (pintype "passive"))
      (node (ref "R92") (pin "2") (pinfunction "2_2") (pintype "passive"))
      (node (ref "U4") (pin "14") (pinfunction "DVDDL_14") (pintype "power_in"))
      (node (ref "U4") (pin "18") (pinfunction "DVDDL_18") (pintype "power_in"))
      (node (ref "U4") (pin "23") (pinfunction "DVDDL_23") (pintype "power_in"))
      (node (ref "U4") (pin "26") (pinfunction "DVDDL_26") (pintype "power_in"))
      (node (ref "U4") (pin "30") (pinfunction "DVDDL_30") (pintype "power_in"))
      (node (ref "U4") (pin "39") (pinfunction "DVDDL_39") (pintype "power_in"))
    )
    (net (code "52") (name "PHY_INT_N") (class "Default")
      (node (ref "R87") (pin "2") (pinfunction "2_2") (pintype "passive"))
    )
    (net (code "53") (name "PHY_MDC") (class "Default")
      (node (ref "R84") (pin "1") (pinfunction "1_1") (pintype "passive"))
    )
    (net (code "54") (name "PHY_MDIO") (class "Default")
      (node (ref "R86") (pin "1") (pinfunction "1_1") (pintype "passive"))
    )
    (net (code "55") (name "PHY_RST_N") (class "Default")
      (node (ref "R83") (pin "2") (pinfunction "2_2") (pintype "passive"))
    )
    (net (code "56") (name "unconnected-(U4A-LDO_O-Pad43)") (class "Default")
      (node (ref "U4") (pin "43") (pinfunction "LDO_O_43") (pintype "output"))
    )
    (net (code "57") (name "unconnected-(U4A-XO-Pad45)") (class "Default")
      (node (ref "U4") (pin "45") (pinfunction "XO_45") (pintype "passive"))
    )
    (net (code "58") (name "unconnected-(U4B-NC-Pad13)") (class "Default")
      (node (ref "U4") (pin "13") (pinfunction "NC_13") (pintype "passive"))
    )
    (net (code "59") (name "unconnected-(U4B-NC-Pad47)") (class "Default")
      (node (ref "U4") (pin "47") (pinfunction "NC_47") (pintype "passive"))
    )
  )
)
